# 03_GSM_GPRS.net
KiCad netlist of a schematic drawn in Altium Designer
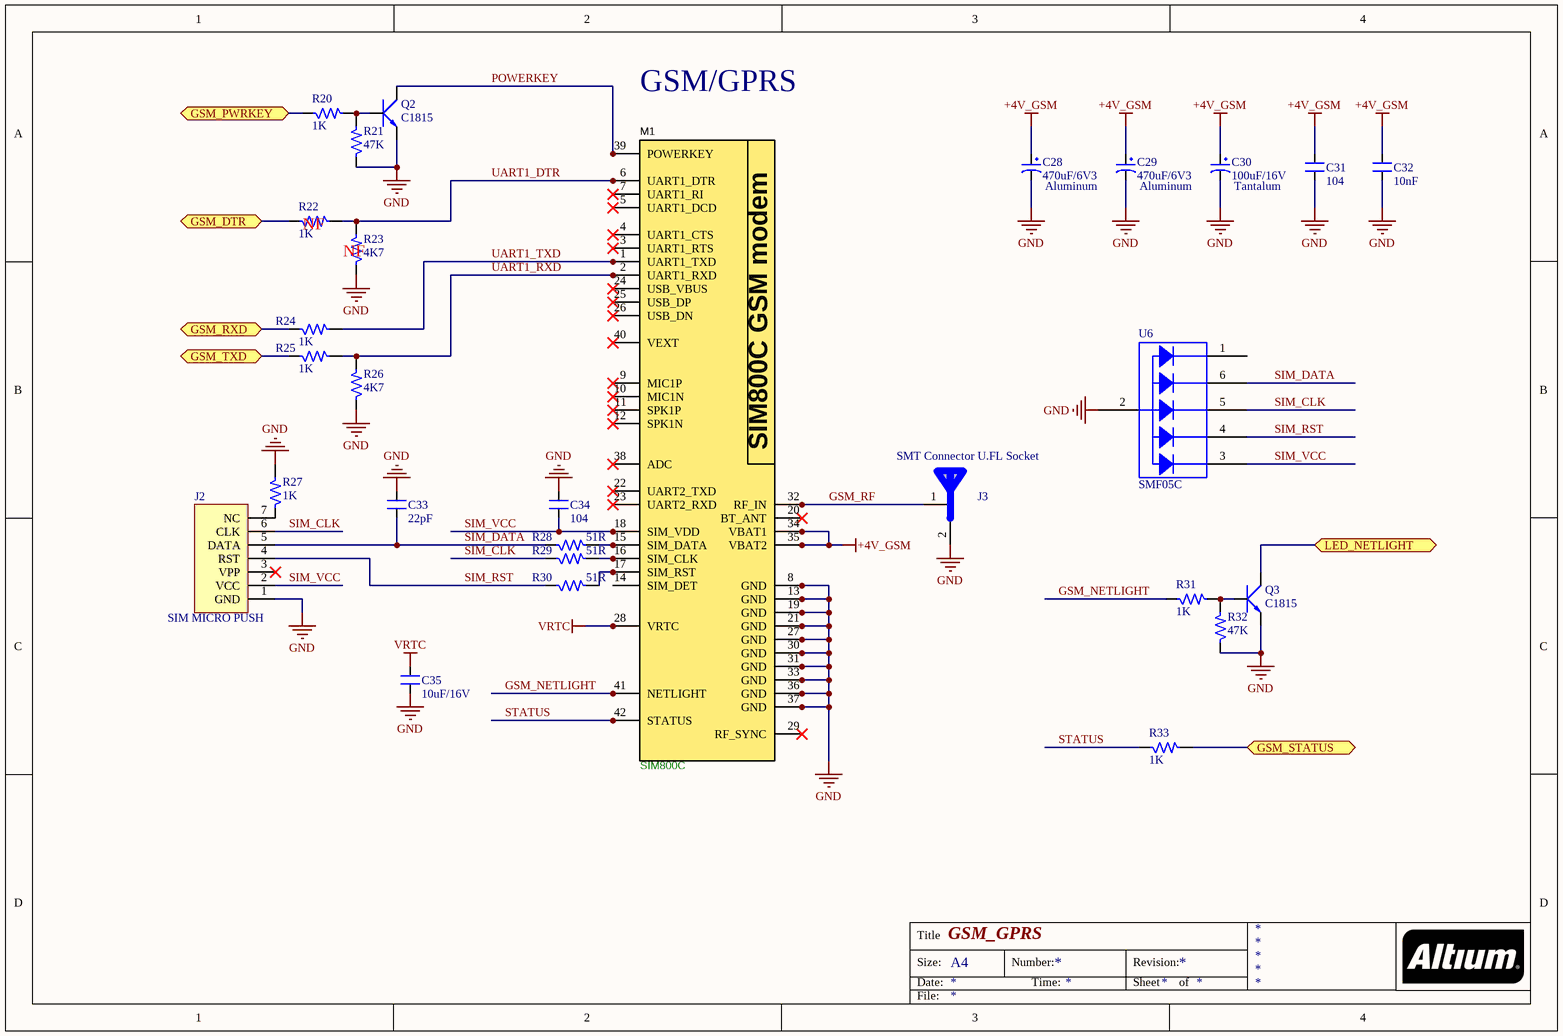
[diagram p0: [03] GSM_GPRS.SchDoc]

(export (version "E")
  (design (tool "Eeschema 10.0.6"))
  (components
    (comp (ref "C28")
      (value "470uF/6V3")
      (footprint "C_Alu_6.3x7.7")
      (description "Cap Aluminum")
      (libsource (lib "khapham") (part "C-Alu-Tantalum"))
    )
    (comp (ref "C29")
      (value "470uF/6V3")
      (footprint "C_Alu_6.3x7.7")
      (description "Cap Aluminum")
      (libsource (lib "khapham") (part "C-Alu-Tantalum"))
    )
    (comp (ref "C30")
      (value "100uF/16V")
      (footprint "C_7343_40")
      (description "Cap Tantalum 7343")
      (libsource (lib "khapham") (part "C-Alu-Tantalum"))
    )
    (comp (ref "C31")
      (value "104")
      (footprint "C0603 SMT")
      (description "Cap SMD")
      (libsource (lib "khapham") (part "CM"))
    )
    (comp (ref "C32")
      (value "10nF")
      (footprint "C0603 SMT")
      (description "Cap SMD")
      (libsource (lib "khapham") (part "CM"))
    )
    (comp (ref "C33")
      (value "22pF")
      (footprint "C0603 SMT")
      (description "Cap SMD")
      (libsource (lib "khapham") (part "CM"))
    )
    (comp (ref "C34")
      (value "104")
      (footprint "C0603 SMT")
      (description "Cap SMD")
      (libsource (lib "khapham") (part "CM"))
    )
    (comp (ref "C35")
      (value "10uF/16V")
      (footprint "C0603 SMT")
      (description "Cap SMD")
      (libsource (lib "khapham") (part "CM"))
    )
    (comp (ref "J2")
      (value "SIM MICRO PUSH")
      (footprint "MicroSim 6P")
      (libsource (lib "khapham") (part "SIM MICRO PUSH"))
    )
    (comp (ref "J3")
      (value "SMT Connector U.FL Socket")
      (footprint "Antenna-IPEX")
      (libsource (lib "khapham") (part "ANTEN"))
    )
    (comp (ref "M1") (value "SIM800C") (footprint "SIM800C") (libsource (lib "khapham") (part "SIM800C")))
    (comp (ref "Q2")
      (value "C1815")
      (footprint "SOT23B")
      (description "NPN 600mW, ECB")
      (libsource (lib "khapham") (part "C1815"))
    )
    (comp (ref "Q3")
      (value "C1815")
      (footprint "SOT23B")
      (description "NPN 600mW, ECB")
      (libsource (lib "khapham") (part "C1815"))
    )
    (comp (ref "R20")
      (value "1K")
      (footprint "R0603 -SMT")
      (description "Resistor SMD")
      (libsource (lib "khapham") (part "RM"))
    )
    (comp (ref "R21")
      (value "47K")
      (footprint "R0603 -SMT")
      (description "Resistor SMD")
      (libsource (lib "khapham") (part "RM"))
    )
    (comp (ref "R22")
      (value "1K")
      (footprint "R0603 -SMT")
      (description "Resistor SMD")
      (libsource (lib "khapham") (part "RM"))
    )
    (comp (ref "R23")
      (value "4K7")
      (footprint "R0603 -SMT")
      (description "Resistor SMD")
      (libsource (lib "khapham") (part "RM"))
    )
    (comp (ref "R24")
      (value "1K")
      (footprint "R0603 -SMT")
      (description "Resistor SMD")
      (libsource (lib "khapham") (part "RM"))
    )
    (comp (ref "R25")
      (value "1K")
      (footprint "R0603 -SMT")
      (description "Resistor SMD")
      (libsource (lib "khapham") (part "RM"))
    )
    (comp (ref "R26")
      (value "4K7")
      (footprint "R0603 -SMT")
      (description "Resistor SMD")
      (libsource (lib "khapham") (part "RM"))
    )
    (comp (ref "R27")
      (value "1K")
      (footprint "R0805 SMT")
      (description "Resistor SMD")
      (libsource (lib "khapham") (part "RM"))
    )
    (comp (ref "R28")
      (value "51R")
      (footprint "R0603 -SMT")
      (description "Resistor SMD")
      (libsource (lib "khapham") (part "RM"))
    )
    (comp (ref "R29")
      (value "51R")
      (footprint "R0603 -SMT")
      (description "Resistor SMD")
      (libsource (lib "khapham") (part "RM"))
    )
    (comp (ref "R30")
      (value "51R")
      (footprint "R0603 -SMT")
      (description "Resistor SMD")
      (libsource (lib "khapham") (part "RM"))
    )
    (comp (ref "R31")
      (value "1K")
      (footprint "R0603 -SMT")
      (description "Resistor SMD")
      (libsource (lib "khapham") (part "RM"))
    )
    (comp (ref "R32")
      (value "47K")
      (footprint "R0603 -SMT")
      (description "Resistor SMD")
      (libsource (lib "khapham") (part "RM"))
    )
    (comp (ref "R33")
      (value "1K")
      (footprint "R0603 -SMT")
      (description "Resistor SMD")
      (libsource (lib "khapham") (part "RM"))
    )
    (comp (ref "U6")
      (value "SMF05C")
      (footprint "SOT_363_6")
      (description "ESD Protection")
      (libsource (lib "khapham") (part "SMF05C"))
    )
  )
  (nets
    (net (code "1") (name "+4V_GSM") (class "Default")
      (node (ref "C28") (pin "1") (pinfunction "1_1") (pintype "passive"))
      (node (ref "C29") (pin "1") (pinfunction "1_1") (pintype "passive"))
      (node (ref "C30") (pin "1") (pinfunction "1_1") (pintype "passive"))
      (node (ref "C31") (pin "1") (pinfunction "1_1") (pintype "passive"))
      (node (ref "C32") (pin "1") (pinfunction "1_1") (pintype "passive"))
      (node (ref "M1") (pin "34") (pinfunction "VBAT1_34") (pintype "passive"))
      (node (ref "M1") (pin "35") (pinfunction "VBAT2_35") (pintype "passive"))
    )
    (net (code "2") (name "/GSM_DTR") (class "Default")
      (node (ref "R22") (pin "1") (pinfunction "1_1") (pintype "passive"))
    )
    (net (code "3") (name "/GSM_NETLIGHT") (class "Default")
      (node (ref "M1") (pin "41") (pinfunction "NETLIGHT_41") (pintype "passive"))
      (node (ref "R31") (pin "1") (pinfunction "1_1") (pintype "passive"))
    )
    (net (code "4") (name "/GSM_PWRKEY") (class "Default")
      (node (ref "R20") (pin "1") (pinfunction "1_1") (pintype "passive"))
    )
    (net (code "5") (name "/GSM_RF") (class "Default")
      (node (ref "J3") (pin "1") (pinfunction "GND_1") (pintype "passive"))
      (node (ref "M1") (pin "32") (pinfunction "RF_IN_32") (pintype "passive"))
    )
    (net (code "6") (name "/GSM_RXD") (class "Default")
      (node (ref "R24") (pin "1") (pinfunction "1_1") (pintype "passive"))
    )
    (net (code "7") (name "/GSM_STATUS") (class "Default")
      (node (ref "R33") (pin "2") (pinfunction "2_2") (pintype "passive"))
    )
    (net (code "8") (name "/GSM_TXD") (class "Default")
      (node (ref "R25") (pin "1") (pinfunction "1_1") (pintype "passive"))
    )
    (net (code "9") (name "/LED_NETLIGHT") (class "Default")
      (node (ref "Q3") (pin "2") (pinfunction "C_2") (pintype "passive"))
    )
    (net (code "10") (name "/POWERKEY") (class "Default")
      (node (ref "M1") (pin "39") (pinfunction "POWERKEY_39") (pintype "passive"))
      (node (ref "Q2") (pin "2") (pinfunction "C_2") (pintype "passive"))
    )
    (net (code "11") (name "/SIM_CLK") (class "Default")
      (node (ref "J2") (pin "6") (pinfunction "CLK_6") (pintype "passive"))
      (node (ref "R29") (pin "1") (pinfunction "1_1") (pintype "passive"))
      (node (ref "U6") (pin "5") (pinfunction "K4_5") (pintype "power_in"))
    )
    (net (code "12") (name "/SIM_DATA") (class "Default")
      (node (ref "C33") (pin "1") (pinfunction "1_1") (pintype "passive"))
      (node (ref "J2") (pin "5") (pinfunction "DATA_5") (pintype "passive"))
      (node (ref "R28") (pin "1") (pinfunction "1_1") (pintype "passive"))
      (node (ref "U6") (pin "6") (pinfunction "K5_6") (pintype "passive"))
    )
    (net (code "13") (name "/SIM_RST") (class "Default")
      (node (ref "J2") (pin "4") (pinfunction "RST_4") (pintype "passive"))
      (node (ref "R30") (pin "1") (pinfunction "1_1") (pintype "passive"))
      (node (ref "U6") (pin "4") (pinfunction "K3_4") (pintype "passive"))
    )
    (net (code "14") (name "/SIM_VCC") (class "Default")
      (node (ref "C34") (pin "1") (pinfunction "1_1") (pintype "passive"))
      (node (ref "J2") (pin "2") (pinfunction "VCC_2") (pintype "passive"))
      (node (ref "M1") (pin "18") (pinfunction "SIM_VDD_18") (pintype "passive"))
      (node (ref "U6") (pin "3") (pinfunction "K2_3") (pintype "passive"))
    )
    (net (code "15") (name "/STATUS") (class "Default")
      (node (ref "M1") (pin "42") (pinfunction "STATUS_42") (pintype "passive"))
      (node (ref "R33") (pin "1") (pinfunction "1_1") (pintype "passive"))
    )
    (net (code "16") (name "/UART1_DTR") (class "Default")
      (node (ref "M1") (pin "6") (pinfunction "UART1_DTR_6") (pintype "passive"))
      (node (ref "R22") (pin "2") (pinfunction "2_2") (pintype "passive"))
      (node (ref "R23") (pin "2") (pinfunction "2_2") (pintype "passive"))
    )
    (net (code "17") (name "/UART1_RXD") (class "Default")
      (node (ref "M1") (pin "2") (pinfunction "UART1_RXD_2") (pintype "passive"))
      (node (ref "R25") (pin "2") (pinfunction "2_2") (pintype "passive"))
      (node (ref "R26") (pin "2") (pinfunction "2_2") (pintype "passive"))
    )
    (net (code "18") (name "/UART1_TXD") (class "Default")
      (node (ref "M1") (pin "1") (pinfunction "UART1_TXD_1") (pintype "passive"))
      (node (ref "R24") (pin "2") (pinfunction "2_2") (pintype "passive"))
    )
    (net (code "19") (name "GND") (class "Default")
      (node (ref "C28") (pin "2") (pinfunction "2_2") (pintype "passive"))
      (node (ref "C29") (pin "2") (pinfunction "2_2") (pintype "passive"))
      (node (ref "C30") (pin "2") (pinfunction "2_2") (pintype "passive"))
      (node (ref "C31") (pin "2") (pinfunction "2_2") (pintype "passive"))
      (node (ref "C32") (pin "2") (pinfunction "2_2") (pintype "passive"))
      (node (ref "C33") (pin "2") (pinfunction "2_2") (pintype "passive"))
      (node (ref "C34") (pin "2") (pinfunction "2_2") (pintype "passive"))
      (node (ref "C35") (pin "2") (pinfunction "2_2") (pintype "passive"))
      (node (ref "J2") (pin "1") (pinfunction "GND_1") (pintype "passive"))
      (node (ref "J3") (pin "2") (pinfunction "GND_2") (pintype "passive"))
      (node (ref "M1") (pin "13") (pinfunction "GND_13") (pintype "passive"))
      (node (ref "M1") (pin "19") (pinfunction "GND_19") (pintype "passive"))
      (node (ref "M1") (pin "21") (pinfunction "GND_21") (pintype "passive"))
      (node (ref "M1") (pin "27") (pinfunction "GND_27") (pintype "passive"))
      (node (ref "M1") (pin "30") (pinfunction "GND_30") (pintype "passive"))
      (node (ref "M1") (pin "31") (pinfunction "GND_31") (pintype "passive"))
      (node (ref "M1") (pin "33") (pinfunction "GND_33") (pintype "passive"))
      (node (ref "M1") (pin "36") (pinfunction "GND_36") (pintype "passive"))
      (node (ref "M1") (pin "37") (pinfunction "GND_37") (pintype "passive"))
      (node (ref "M1") (pin "8") (pinfunction "GND_8") (pintype "passive"))
      (node (ref "Q2") (pin "1") (pinfunction "E_1") (pintype "passive"))
      (node (ref "Q3") (pin "1") (pinfunction "E_1") (pintype "passive"))
      (node (ref "R21") (pin "1") (pinfunction "1_1") (pintype "passive"))
      (node (ref "R23") (pin "1") (pinfunction "1_1") (pintype "passive"))
      (node (ref "R26") (pin "1") (pinfunction "1_1") (pintype "passive"))
      (node (ref "R27") (pin "2") (pinfunction "2_2") (pintype "passive"))
      (node (ref "R32") (pin "1") (pinfunction "1_1") (pintype "passive"))
      (node (ref "U6") (pin "2") (pinfunction "A_2") (pintype "power_in"))
    )
    (net (code "20") (name "Net-(J2-NC)") (class "Default")
      (node (ref "J2") (pin "7") (pinfunction "NC_7") (pintype "passive"))
      (node (ref "R27") (pin "1") (pinfunction "1_1") (pintype "passive"))
    )
    (net (code "21") (name "Net-(M1-SIM_CLK)") (class "Default")
      (node (ref "M1") (pin "16") (pinfunction "SIM_CLK_16") (pintype "passive"))
      (node (ref "R29") (pin "2") (pinfunction "2_2") (pintype "passive"))
    )
    (net (code "22") (name "Net-(M1-SIM_DATA)") (class "Default")
      (node (ref "M1") (pin "15") (pinfunction "SIM_DATA_15") (pintype "passive"))
      (node (ref "R28") (pin "2") (pinfunction "2_2") (pintype "passive"))
    )
    (net (code "23") (name "Net-(M1-SIM_RST)") (class "Default")
      (node (ref "M1") (pin "17") (pinfunction "SIM_RST_17") (pintype "passive"))
      (node (ref "R30") (pin "2") (pinfunction "2_2") (pintype "passive"))
    )
    (net (code "24") (name "Net-(Q2-B)") (class "Default")
      (node (ref "Q2") (pin "3") (pinfunction "B_3") (pintype "passive"))
      (node (ref "R20") (pin "2") (pinfunction "2_2") (pintype "passive"))
      (node (ref "R21") (pin "2") (pinfunction "2_2") (pintype "passive"))
    )
    (net (code "25") (name "Net-(Q3-B)") (class "Default")
      (node (ref "Q3") (pin "3") (pinfunction "B_3") (pintype "passive"))
      (node (ref "R31") (pin "2") (pinfunction "2_2") (pintype "passive"))
      (node (ref "R32") (pin "2") (pinfunction "2_2") (pintype "passive"))
    )
    (net (code "26") (name "VRTC") (class "Default")
      (node (ref "C35") (pin "1") (pinfunction "1_1") (pintype "passive"))
      (node (ref "M1") (pin "28") (pinfunction "VRTC_28") (pintype "passive"))
    )
    (net (code "27") (name "unconnected-(J2-VPP-Pad3)") (class "Default")
      (node (ref "J2") (pin "3") (pinfunction "VPP_3") (pintype "passive+no_connect"))
    )
    (net (code "28") (name "unconnected-(M1-ADC-Pad38)") (class "Default")
      (node (ref "M1") (pin "38") (pinfunction "ADC_38") (pintype "passive+no_connect"))
    )
    (net (code "29") (name "unconnected-(M1-BT_ANT-Pad20)") (class "Default")
      (node (ref "M1") (pin "20") (pinfunction "BT_ANT_20") (pintype "passive+no_connect"))
    )
    (net (code "30") (name "unconnected-(M1-MIC1N-Pad10)") (class "Default")
      (node (ref "M1") (pin "10") (pinfunction "MIC1N_10") (pintype "passive+no_connect"))
    )
    (net (code "31") (name "unconnected-(M1-MIC1P-Pad9)") (class "Default")
      (node (ref "M1") (pin "9") (pinfunction "MIC1P_9") (pintype "passive+no_connect"))
    )
    (net (code "32") (name "unconnected-(M1-RF_SYNC-Pad29)") (class "Default")
      (node (ref "M1") (pin "29") (pinfunction "RF_SYNC_29") (pintype "passive+no_connect"))
    )
    (net (code "33") (name "unconnected-(M1-SIM_DET-Pad14)") (class "Default")
      (node (ref "M1") (pin "14") (pinfunction "SIM_DET_14") (pintype "passive"))
    )
    (net (code "34") (name "unconnected-(M1-SPK1N-Pad12)") (class "Default")
      (node (ref "M1") (pin "12") (pinfunction "SPK1N_12") (pintype "passive+no_connect"))
    )
    (net (code "35") (name "unconnected-(M1-SPK1P-Pad11)") (class "Default")
      (node (ref "M1") (pin "11") (pinfunction "SPK1P_11") (pintype "passive+no_connect"))
    )
    (net (code "36") (name "unconnected-(M1-UART1_CTS-Pad4)") (class "Default")
      (node (ref "M1") (pin "4") (pinfunction "UART1_CTS_4") (pintype "passive+no_connect"))
    )
    (net (code "37") (name "unconnected-(M1-UART1_DCD-Pad5)") (class "Default")
      (node (ref "M1") (pin "5") (pinfunction "UART1_DCD_5") (pintype "passive+no_connect"))
    )
    (net (code "38") (name "unconnected-(M1-UART1_RI-Pad7)") (class "Default")
      (node (ref "M1") (pin "7") (pinfunction "UART1_RI_7") (pintype "passive+no_connect"))
    )
    (net (code "39") (name "unconnected-(M1-UART1_RTS-Pad3)") (class "Default")
      (node (ref "M1") (pin "3") (pinfunction "UART1_RTS_3") (pintype "passive+no_connect"))
    )
    (net (code "40") (name "unconnected-(M1-UART2_RXD-Pad23)") (class "Default")
      (node (ref "M1") (pin "23") (pinfunction "UART2_RXD_23") (pintype "passive+no_connect"))
    )
    (net (code "41") (name "unconnected-(M1-UART2_TXD-Pad22)") (class "Default")
      (node (ref "M1") (pin "22") (pinfunction "UART2_TXD_22") (pintype "passive+no_connect"))
    )
    (net (code "42") (name "unconnected-(M1-USB_DN-Pad26)") (class "Default")
      (node (ref "M1") (pin "26") (pinfunction "USB_DN_26") (pintype "passive+no_connect"))
    )
    (net (code "43") (name "unconnected-(M1-USB_DP-Pad25)") (class "Default")
      (node (ref "M1") (pin "25") (pinfunction "USB_DP_25") (pintype "passive+no_connect"))
    )
    (net (code "44") (name "unconnected-(M1-USB_VBUS-Pad24)") (class "Default")
      (node (ref "M1") (pin "24") (pinfunction "USB_VBUS_24") (pintype "passive+no_connect"))
    )
    (net (code "45") (name "unconnected-(M1-VEXT-Pad40)") (class "Default")
      (node (ref "M1") (pin "40") (pinfunction "VEXT_40") (pintype "passive+no_connect"))
    )
    (net (code "46") (name "unconnected-(U6-K1-Pad1)") (class "Default")
      (node (ref "U6") (pin "1") (pinfunction "K1_1") (pintype "passive"))
    )
  )
)
